# daughter-mux.net
KiCad netlist of a schematic drawn in EAGLE
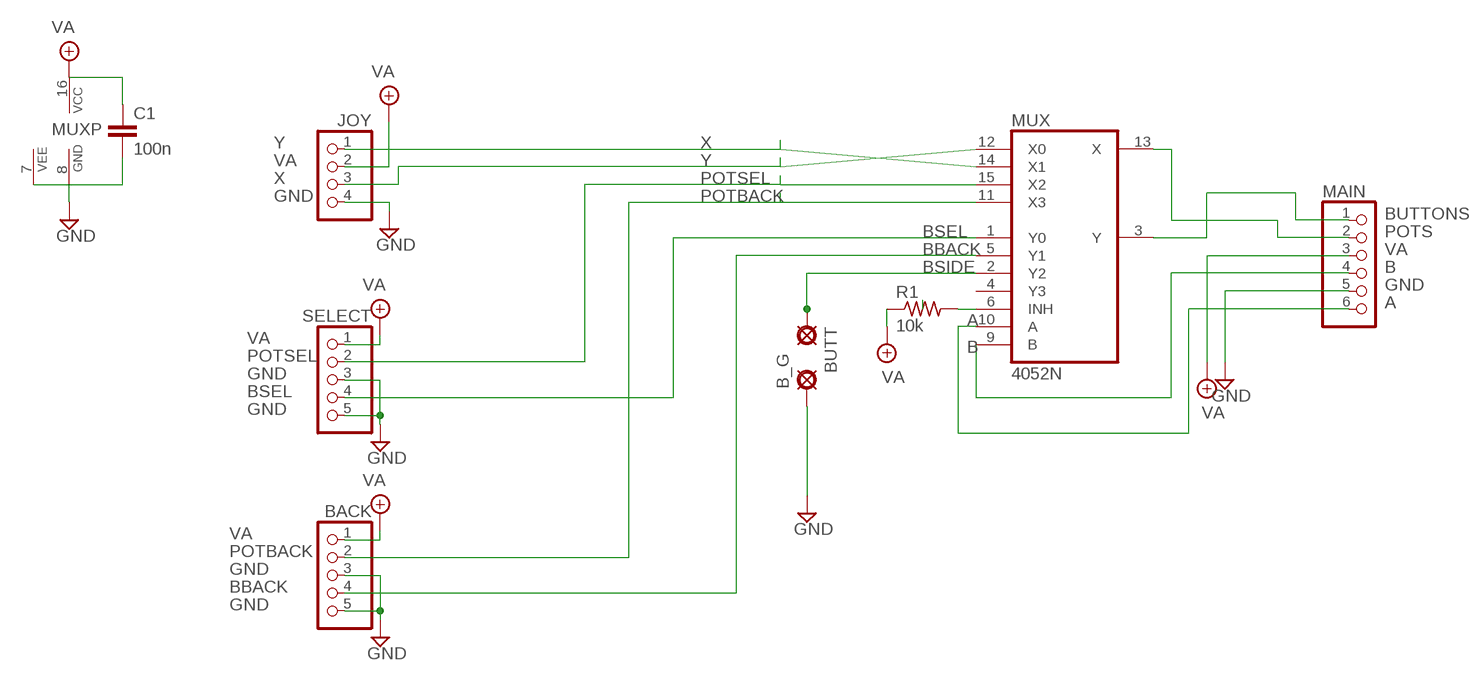
[diagram p0: schematic, sheet 1]

(export (version "E")
  (design (tool "Eeschema 10.0.6"))
  (components
    (comp (ref "BACK")
      (value "PINHD-1X5")
      (footprint "eagle-import:1X05")
      (libsource (lib "eagle-import") (part "PINHD-1X5"))
    )
    (comp (ref "BUTT")
      (value "PAD")
      (footprint "eagle-import:SQUARE")
      (libsource (lib "eagle-import") (part "PAD"))
    )
    (comp (ref "B_G")
      (value "PAD8")
      (footprint "eagle-import:OCTOGON")
      (libsource (lib "eagle-import") (part "PAD8"))
    )
    (comp (ref "C1")
      (value "100n")
      (footprint "eagle-import:050X030_050_3")
      (libsource (lib "eagle-import") (part "050X030_050"))
    )
    (comp (ref "JOY")
      (value "PINHD-1X4")
      (footprint "eagle-import:1X04")
      (libsource (lib "eagle-import") (part "PINHD-1X4"))
    )
    (comp (ref "MAIN")
      (value "PINHD-1X6")
      (footprint "eagle-import:1X06")
      (libsource (lib "eagle-import") (part "PINHD-1X6"))
    )
    (comp (ref "MUX")
      (value "4052N")
      (footprint "eagle-import:DIL16")
      (libsource (lib "eagle-import") (part "4052N"))
    )
    (comp (ref "R1")
      (value "10k")
      (footprint "eagle-import:R0207_6")
      (libsource (lib "eagle-import") (part "6MM.6"))
    )
    (comp (ref "SELECT")
      (value "PINHD-1X5")
      (footprint "eagle-import:1X05")
      (libsource (lib "eagle-import") (part "PINHD-1X5"))
    )
  )
  (nets
    (net (code "1") (name "/A") (class "Default")
      (node (ref "MAIN") (pin "6") (pinfunction "6_6") (pintype "passive"))
      (node (ref "MUX") (pin "10") (pinfunction "A_10") (pintype "input"))
    )
    (net (code "2") (name "/B") (class "Default")
      (node (ref "MAIN") (pin "4") (pinfunction "4_4") (pintype "passive"))
      (node (ref "MUX") (pin "9") (pinfunction "B_9") (pintype "input"))
    )
    (net (code "3") (name "/BBACK") (class "Default")
      (node (ref "BACK") (pin "4") (pinfunction "4_4") (pintype "passive"))
      (node (ref "MUX") (pin "5") (pinfunction "Y1_5") (pintype "bidirectional"))
    )
    (net (code "4") (name "/BSEL") (class "Default")
      (node (ref "MUX") (pin "1") (pinfunction "Y0_1") (pintype "bidirectional"))
      (node (ref "SELECT") (pin "4") (pinfunction "4_4") (pintype "passive"))
    )
    (net (code "5") (name "/BSIDE") (class "Default")
      (node (ref "BUTT") (pin "1") (pinfunction "PAD_1") (pintype "passive"))
      (node (ref "MUX") (pin "2") (pinfunction "Y2_2") (pintype "bidirectional"))
    )
    (net (code "6") (name "/BUTTONS") (class "Default")
      (node (ref "MAIN") (pin "1") (pinfunction "1_1") (pintype "passive"))
      (node (ref "MUX") (pin "3") (pinfunction "Y_3") (pintype "bidirectional"))
    )
    (net (code "7") (name "/POTBACK") (class "Default")
      (node (ref "BACK") (pin "2") (pinfunction "2_2") (pintype "passive"))
      (node (ref "MUX") (pin "11") (pinfunction "X3_11") (pintype "bidirectional"))
    )
    (net (code "8") (name "/POTS") (class "Default")
      (node (ref "MAIN") (pin "2") (pinfunction "2_2") (pintype "passive"))
      (node (ref "MUX") (pin "13") (pinfunction "X_13") (pintype "bidirectional"))
    )
    (net (code "9") (name "/POTSEL") (class "Default")
      (node (ref "MUX") (pin "15") (pinfunction "X2_15") (pintype "bidirectional"))
      (node (ref "SELECT") (pin "2") (pinfunction "2_2") (pintype "passive"))
    )
    (net (code "10") (name "/X") (class "Default")
      (node (ref "JOY") (pin "1") (pinfunction "1_1") (pintype "passive"))
      (node (ref "MUX") (pin "14") (pinfunction "X1_14") (pintype "bidirectional"))
    )
    (net (code "11") (name "/Y") (class "Default")
      (node (ref "JOY") (pin "3") (pinfunction "3_3") (pintype "passive"))
      (node (ref "MUX") (pin "12") (pinfunction "X0_12") (pintype "bidirectional"))
    )
    (net (code "12") (name "GND") (class "Default")
      (node (ref "BACK") (pin "3") (pinfunction "3_3") (pintype "passive"))
      (node (ref "BACK") (pin "5") (pinfunction "5_5") (pintype "passive"))
      (node (ref "B_G") (pin "1") (pinfunction "PAD_1") (pintype "passive"))
      (node (ref "C1") (pin "2") (pinfunction "2_2") (pintype "passive"))
      (node (ref "JOY") (pin "4") (pinfunction "4_4") (pintype "passive"))
      (node (ref "MAIN") (pin "5") (pinfunction "5_5") (pintype "passive"))
      (node (ref "MUX") (pin "7") (pinfunction "VEE_7") (pintype "power_in"))
      (node (ref "MUX") (pin "8") (pinfunction "GND_8") (pintype "power_in"))
      (node (ref "SELECT") (pin "3") (pinfunction "3_3") (pintype "passive"))
      (node (ref "SELECT") (pin "5") (pinfunction "5_5") (pintype "passive"))
    )
    (net (code "13") (name "Net-(MUXA-INH)") (class "Default")
      (node (ref "MUX") (pin "6") (pinfunction "INH_6") (pintype "input"))
      (node (ref "R1") (pin "2") (pinfunction "2_2") (pintype "passive"))
    )
    (net (code "14") (name "VA") (class "Default")
      (node (ref "BACK") (pin "1") (pinfunction "1_1") (pintype "passive"))
      (node (ref "C1") (pin "1") (pinfunction "1_1") (pintype "passive"))
      (node (ref "JOY") (pin "2") (pinfunction "2_2") (pintype "passive"))
      (node (ref "MAIN") (pin "3") (pinfunction "3_3") (pintype "passive"))
      (node (ref "MUX") (pin "16") (pinfunction "VCC_16") (pintype "power_in"))
      (node (ref "R1") (pin "1") (pinfunction "1_1") (pintype "passive"))
      (node (ref "SELECT") (pin "1") (pinfunction "1_1") (pintype "passive"))
    )
    (net (code "15") (name "unconnected-(MUXA-Y3-Pad4)") (class "Default")
      (node (ref "MUX") (pin "4") (pinfunction "Y3_4") (pintype "bidirectional"))
    )
  )
)
